# Uno.net
KiCad netlist of a schematic drawn in EAGLE
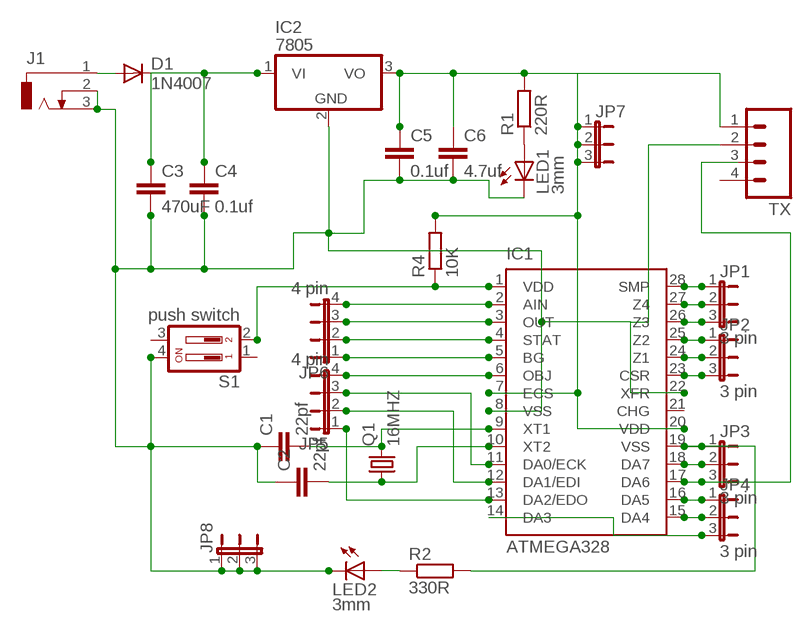
[diagram p0: schematic, sheet 1]

(export (version "E")
  (design (tool "Eeschema 10.0.6"))
  (components
    (comp (ref "C1")
      (value "22pf")
      (footprint "eagle-import:C2.5-2")
      (libsource (lib "eagle-import") (part "C2.5/2"))
    )
    (comp (ref "C2")
      (value "22pf")
      (footprint "eagle-import:C2.5-2")
      (libsource (lib "eagle-import") (part "C2.5/2"))
    )
    (comp (ref "C3")
      (value "470uF")
      (footprint "eagle-import:C2.5-2")
      (libsource (lib "eagle-import") (part "C2.5/2"))
    )
    (comp (ref "C4")
      (value "0.1uf")
      (footprint "eagle-import:C2.5-2")
      (libsource (lib "eagle-import") (part "C2.5/2"))
    )
    (comp (ref "C5")
      (value "0.1uf")
      (footprint "eagle-import:C2.5-2")
      (libsource (lib "eagle-import") (part "C2.5/2"))
    )
    (comp (ref "C6")
      (value "4.7uf")
      (footprint "eagle-import:C2.5-2")
      (libsource (lib "eagle-import") (part "C2.5/2"))
    )
    (comp (ref "D1")
      (value "1N4007")
      (footprint "eagle-import:DO41-10")
      (libsource (lib "eagle-import") (part "1N4004"))
    )
    (comp (ref "IC1")
      (value "ATMEGA328")
      (footprint "eagle-import:DIL28-3")
      (libsource (lib "eagle-import") (part "QT9701BD"))
    )
    (comp (ref "IC2")
      (value "7805")
      (footprint "eagle-import:TO220V")
      (libsource (lib "eagle-import") (part "78TV6"))
    )
    (comp (ref "J1")
      (value "DCJ0303")
      (footprint "eagle-import:DCJ0303")
      (libsource (lib "eagle-import") (part "DCJ0303"))
    )
    (comp (ref "JP1")
      (value "3 pin")
      (footprint "eagle-import:JP2")
      (libsource (lib "eagle-import") (part "JP2E"))
    )
    (comp (ref "JP2")
      (value "3 pin")
      (footprint "eagle-import:JP2")
      (libsource (lib "eagle-import") (part "JP2E"))
    )
    (comp (ref "JP3")
      (value "3 pin")
      (footprint "eagle-import:JP2")
      (libsource (lib "eagle-import") (part "JP2E"))
    )
    (comp (ref "JP4")
      (value "3 pin")
      (footprint "eagle-import:JP2")
      (libsource (lib "eagle-import") (part "JP2E"))
    )
    (comp (ref "JP5")
      (value "4 pin")
      (footprint "eagle-import:JP4")
      (libsource (lib "eagle-import") (part "JP4E"))
    )
    (comp (ref "JP6")
      (value "4 pin")
      (footprint "eagle-import:JP4")
      (libsource (lib "eagle-import") (part "JP4E"))
    )
    (comp (ref "JP7")
      (value "JP2E")
      (footprint "eagle-import:JP2")
      (libsource (lib "eagle-import") (part "JP2E"))
    )
    (comp (ref "JP8")
      (value "JP2E")
      (footprint "eagle-import:JP2")
      (libsource (lib "eagle-import") (part "JP2E"))
    )
    (comp (ref "LED1")
      (value "3mm")
      (footprint "eagle-import:LED3MM")
      (libsource (lib "eagle-import") (part "LED3MM"))
    )
    (comp (ref "LED2")
      (value "3mm")
      (footprint "eagle-import:LED3MM")
      (libsource (lib "eagle-import") (part "LED3MM"))
    )
    (comp (ref "Q1")
      (value "16MHZ")
      (footprint "eagle-import:HC49_S")
      (libsource (lib "eagle-import") (part "CRYSTALHC49S"))
    )
    (comp (ref "R1")
      (value "220R")
      (footprint "eagle-import:0207_10")
      (libsource (lib "eagle-import") (part "R-EU_0207/10"))
    )
    (comp (ref "R2")
      (value "330R")
      (footprint "eagle-import:0207_10")
      (libsource (lib "eagle-import") (part "R-EU_0207/10"))
    )
    (comp (ref "R4")
      (value "10K")
      (footprint "eagle-import:0207_10")
      (libsource (lib "eagle-import") (part "R-EU_0207/10"))
    )
    (comp (ref "S1")
      (value "push switch")
      (footprint "eagle-import:DP-02")
      (fields (field (name "MPN") "MCDP02"))
      (libsource (lib "eagle-import") (part "DP02"))
    )
    (comp (ref "TX")
      (value "M04")
      (footprint "eagle-import:04P")
      (libsource (lib "eagle-import") (part "M04"))
    )
  )
  (nets
    (net (code "1") (name "Net-(D1-PadA)") (class "Default")
      (node (ref "D1") (pin "A") (pinfunction "A_A") (pintype "passive"))
      (node (ref "J1") (pin "1") (pinfunction "1_1") (pintype "passive"))
    )
    (net (code "2") (name "Net-(IC1-AIN)") (class "Default")
      (node (ref "IC1") (pin "2") (pinfunction "AIN_2") (pintype "input"))
      (node (ref "JP6") (pin "4") (pinfunction "4_4") (pintype "passive"))
    )
    (net (code "3") (name "Net-(IC1-BG)") (class "Default")
      (node (ref "IC1") (pin "5") (pinfunction "BG_5") (pintype "input"))
      (node (ref "JP6") (pin "1") (pinfunction "1_1") (pintype "passive"))
    )
    (net (code "4") (name "Net-(IC1-CSR)") (class "Default")
      (node (ref "IC1") (pin "23") (pinfunction "CSR_23") (pintype "output"))
      (node (ref "JP2") (pin "3") (pinfunction "3_3") (pintype "passive"))
    )
    (net (code "5") (name "Net-(IC1-DA0{slash}ECK)") (class "Default")
      (node (ref "IC1") (pin "11") (pinfunction "DA0/ECK_11") (pintype "output"))
      (node (ref "JP5") (pin "3") (pinfunction "3_3") (pintype "passive"))
    )
    (net (code "6") (name "Net-(IC1-DA1{slash}EDI)") (class "Default")
      (node (ref "IC1") (pin "12") (pinfunction "DA1/EDI_12") (pintype "output"))
      (node (ref "JP5") (pin "2") (pinfunction "2_2") (pintype "passive"))
    )
    (net (code "7") (name "Net-(IC1-DA2{slash}EDO)") (class "Default")
      (node (ref "IC1") (pin "13") (pinfunction "DA2/EDO_13") (pintype "output"))
      (node (ref "JP5") (pin "1") (pinfunction "1_1") (pintype "passive"))
    )
    (net (code "8") (name "Net-(IC1-DA3)") (class "Default")
      (node (ref "IC1") (pin "14") (pinfunction "DA3_14") (pintype "output"))
      (node (ref "JP4") (pin "3") (pinfunction "3_3") (pintype "passive"))
    )
    (net (code "9") (name "Net-(IC1-DA4)") (class "Default")
      (node (ref "IC1") (pin "15") (pinfunction "DA4_15") (pintype "output"))
      (node (ref "JP4") (pin "2") (pinfunction "2_2") (pintype "passive"))
    )
    (net (code "10") (name "Net-(IC1-DA5)") (class "Default")
      (node (ref "IC1") (pin "16") (pinfunction "DA5_16") (pintype "output"))
      (node (ref "JP4") (pin "1") (pinfunction "1_1") (pintype "passive"))
    )
    (net (code "11") (name "Net-(IC1-DA6)") (class "Default")
      (node (ref "IC1") (pin "17") (pinfunction "DA6_17") (pintype "output"))
      (node (ref "JP3") (pin "3") (pinfunction "3_3") (pintype "passive"))
      (node (ref "TX") (pin "3") (pinfunction "3_3") (pintype "passive"))
    )
    (net (code "12") (name "Net-(IC1-DA7)") (class "Default")
      (node (ref "IC1") (pin "18") (pinfunction "DA7_18") (pintype "output"))
      (node (ref "JP3") (pin "2") (pinfunction "2_2") (pintype "passive"))
    )
    (net (code "13") (name "Net-(IC1-ECS)") (class "Default")
      (node (ref "C5") (pin "1") (pinfunction "1_1") (pintype "passive"))
      (node (ref "C6") (pin "1") (pinfunction "1_1") (pintype "passive"))
      (node (ref "IC1") (pin "20") (pinfunction "VDD_20") (pintype "input"))
      (node (ref "IC1") (pin "7") (pinfunction "ECS_7") (pintype "output"))
      (node (ref "IC2") (pin "3") (pinfunction "VO_3") (pintype "passive"))
      (node (ref "JP7") (pin "1") (pinfunction "1_1") (pintype "passive"))
      (node (ref "JP7") (pin "2") (pinfunction "2_2") (pintype "passive"))
      (node (ref "JP7") (pin "3") (pinfunction "3_3") (pintype "passive"))
      (node (ref "R1") (pin "2") (pinfunction "2_2") (pintype "passive"))
      (node (ref "R4") (pin "2") (pinfunction "2_2") (pintype "passive"))
      (node (ref "TX") (pin "1") (pinfunction "1_1") (pintype "passive"))
    )
    (net (code "14") (name "Net-(IC1-OBJ)") (class "Default")
      (node (ref "IC1") (pin "6") (pinfunction "OBJ_6") (pintype "input"))
      (node (ref "JP5") (pin "4") (pinfunction "4_4") (pintype "passive"))
    )
    (net (code "15") (name "Net-(IC1-OUT)") (class "Default")
      (node (ref "IC1") (pin "3") (pinfunction "OUT_3") (pintype "output"))
      (node (ref "JP6") (pin "3") (pinfunction "3_3") (pintype "passive"))
    )
    (net (code "16") (name "Net-(IC1-SMP)") (class "Default")
      (node (ref "IC1") (pin "28") (pinfunction "SMP_28") (pintype "output"))
      (node (ref "JP1") (pin "1") (pinfunction "1_1") (pintype "passive"))
    )
    (net (code "17") (name "Net-(IC1-STAT)") (class "Default")
      (node (ref "IC1") (pin "4") (pinfunction "STAT_4") (pintype "output"))
      (node (ref "JP6") (pin "2") (pinfunction "2_2") (pintype "passive"))
    )
    (net (code "18") (name "Net-(IC1-VDD-Pad1)") (class "Default")
      (node (ref "IC1") (pin "1") (pinfunction "VDD_1") (pintype "input"))
      (node (ref "R4") (pin "1") (pinfunction "1_1") (pintype "passive"))
      (node (ref "S1") (pin "2") (pinfunction "2_2") (pintype "passive"))
    )
    (net (code "19") (name "Net-(IC1-VSS-Pad19)") (class "Default")
      (node (ref "IC1") (pin "19") (pinfunction "VSS_19") (pintype "input"))
      (node (ref "JP3") (pin "1") (pinfunction "1_1") (pintype "passive"))
      (node (ref "R2") (pin "2") (pinfunction "2_2") (pintype "passive"))
    )
    (net (code "20") (name "Net-(IC1-XFR)") (class "Default")
      (node (ref "C1") (pin "1") (pinfunction "1_1") (pintype "passive"))
      (node (ref "C2") (pin "1") (pinfunction "1_1") (pintype "passive"))
      (node (ref "C3") (pin "2") (pinfunction "2_2") (pintype "passive"))
      (node (ref "C4") (pin "2") (pinfunction "2_2") (pintype "passive"))
      (node (ref "C5") (pin "2") (pinfunction "2_2") (pintype "passive"))
      (node (ref "C6") (pin "2") (pinfunction "2_2") (pintype "passive"))
      (node (ref "IC1") (pin "22") (pinfunction "XFR_22") (pintype "output"))
      (node (ref "IC1") (pin "8") (pinfunction "VSS_8") (pintype "input"))
      (node (ref "IC2") (pin "2") (pinfunction "GND_2") (pintype "passive"))
      (node (ref "J1") (pin "2") (pinfunction "2_2") (pintype "passive"))
      (node (ref "J1") (pin "3") (pinfunction "3_3") (pintype "passive"))
      (node (ref "JP8") (pin "1") (pinfunction "1_1") (pintype "passive"))
      (node (ref "JP8") (pin "2") (pinfunction "2_2") (pintype "passive"))
      (node (ref "JP8") (pin "3") (pinfunction "3_3") (pintype "passive"))
      (node (ref "LED1") (pin "K") (pinfunction "C_K") (pintype "passive"))
      (node (ref "LED2") (pin "K") (pinfunction "C_K") (pintype "passive"))
      (node (ref "S1") (pin "4") (pinfunction "4_4") (pintype "passive"))
      (node (ref "TX") (pin "2") (pinfunction "2_2") (pintype "passive"))
    )
    (net (code "21") (name "Net-(IC1-XT1)") (class "Default")
      (node (ref "C1") (pin "2") (pinfunction "2_2") (pintype "passive"))
      (node (ref "IC1") (pin "9") (pinfunction "XT1_9") (pintype "input"))
      (node (ref "Q1") (pin "2") (pinfunction "2_2") (pintype "passive"))
    )
    (net (code "22") (name "Net-(IC1-XT2)") (class "Default")
      (node (ref "C2") (pin "2") (pinfunction "2_2") (pintype "passive"))
      (node (ref "IC1") (pin "10") (pinfunction "XT2_10") (pintype "output"))
      (node (ref "Q1") (pin "1") (pinfunction "1_1") (pintype "passive"))
    )
    (net (code "23") (name "Net-(IC1-Z1)") (class "Default")
      (node (ref "IC1") (pin "24") (pinfunction "Z1_24") (pintype "output"))
      (node (ref "JP2") (pin "2") (pinfunction "2_2") (pintype "passive"))
    )
    (net (code "24") (name "Net-(IC1-Z2)") (class "Default")
      (node (ref "IC1") (pin "25") (pinfunction "Z2_25") (pintype "output"))
      (node (ref "JP2") (pin "1") (pinfunction "1_1") (pintype "passive"))
    )
    (net (code "25") (name "Net-(IC1-Z3)") (class "Default")
      (node (ref "IC1") (pin "26") (pinfunction "Z3_26") (pintype "output"))
      (node (ref "JP1") (pin "3") (pinfunction "3_3") (pintype "passive"))
    )
    (net (code "26") (name "Net-(IC1-Z4)") (class "Default")
      (node (ref "IC1") (pin "27") (pinfunction "Z4_27") (pintype "output"))
      (node (ref "JP1") (pin "2") (pinfunction "2_2") (pintype "passive"))
    )
    (net (code "27") (name "Net-(IC2-VI)") (class "Default")
      (node (ref "C3") (pin "1") (pinfunction "1_1") (pintype "passive"))
      (node (ref "C4") (pin "1") (pinfunction "1_1") (pintype "passive"))
      (node (ref "D1") (pin "C") (pinfunction "C_C") (pintype "passive"))
      (node (ref "IC2") (pin "1") (pinfunction "VI_1") (pintype "input"))
    )
    (net (code "28") (name "Net-(LED1-PadA)") (class "Default")
      (node (ref "LED1") (pin "A") (pinfunction "A_A") (pintype "passive"))
      (node (ref "R1") (pin "1") (pinfunction "1_1") (pintype "passive"))
    )
    (net (code "29") (name "Net-(LED2-PadA)") (class "Default")
      (node (ref "LED2") (pin "A") (pinfunction "A_A") (pintype "passive"))
      (node (ref "R2") (pin "1") (pinfunction "1_1") (pintype "passive"))
    )
    (net (code "30") (name "unconnected-(IC1-CHG-Pad21)") (class "Default")
      (node (ref "IC1") (pin "21") (pinfunction "CHG_21") (pintype "output"))
    )
    (net (code "31") (name "unconnected-(S1-Pad1)") (class "Default")
      (node (ref "S1") (pin "1") (pinfunction "1_1") (pintype "passive"))
    )
    (net (code "32") (name "unconnected-(S1-Pad3)") (class "Default")
      (node (ref "S1") (pin "3") (pinfunction "3_3") (pintype "passive"))
    )
    (net (code "33") (name "unconnected-(TX-Pad4)") (class "Default")
      (node (ref "TX") (pin "4") (pinfunction "4_4") (pintype "passive"))
    )
  )
)
